# Top.net
KiCad netlist of a schematic drawn in Altium Designer
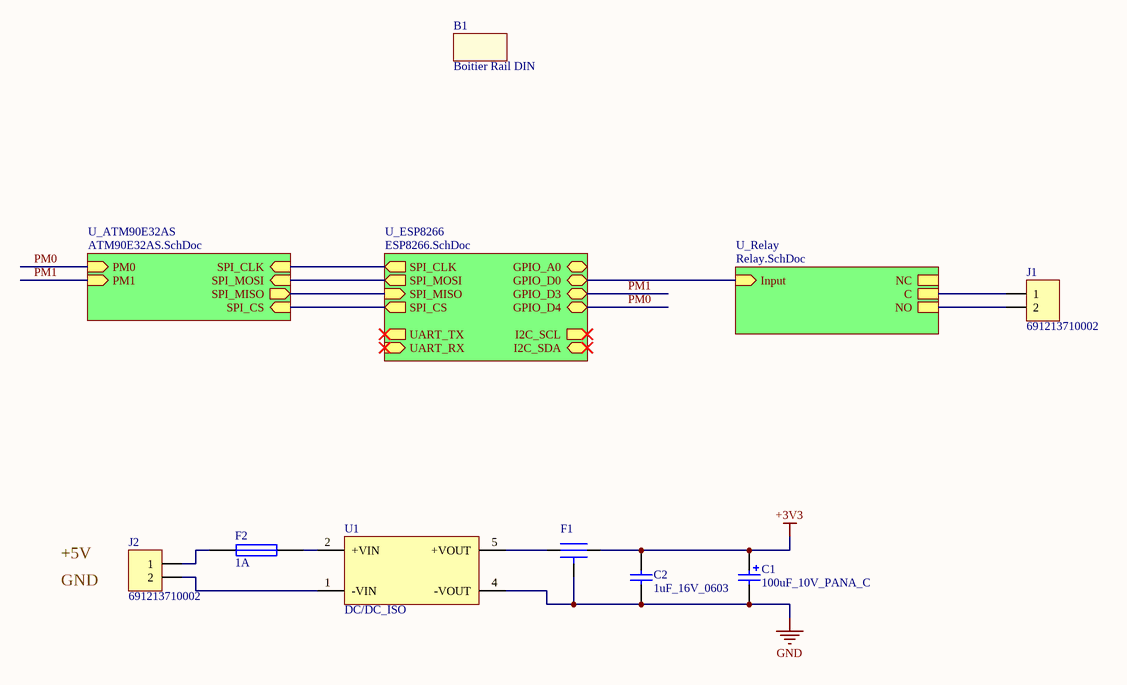
[diagram p0: Top.SchDoc]

(export (version "E")
  (design (tool "Eeschema 10.0.6"))
  (components
    (comp (ref "B1")
      (value "Boitier Rail DIN")
      (description "Part of schematic")
      (fields (field (name "MF") "BUD INDUSTRIES") (field (name "MPN") "DMB4771"))
      (libsource (lib "Common") (part "Component"))
    )
    (comp (ref "C1")
      (value "100uF_10V_PANA_C")
      (footprint "CAP_PANA_C")
      (description "Polarized Capacitor (Radial)")
      (fields (field (name "MF") "PANASONIC ELECTRONIC COMPONENTS") (field (name "MPN") "EEE1AA101WR"))
      (libsource (lib "Common") (part "Cap Pol"))
    )
    (comp (ref "C2")
      (value "1uF_16V_0603")
      (footprint "C0603")
      (description "Capacitor")
      (fields (field (name "MF") "WURTH ELEKTRONIK") (field (name "MPN") "885012106017"))
      (libsource (lib "Common") (part "Cap"))
    )
    (comp (ref "F1")
      (value "EMI")
      (footprint "EMIFIL_0603")
      (description "FILTER CAP 0.1UF 2A 16V 0603")
      (fields (field (name "MF") "MURATA") (field (name "MPN") "NFM18PC104R1C3D"))
      (libsource (lib "Common") (part "EMIFIL_0603"))
    )
    (comp (ref "F2")
      (value "1A")
      (footprint "R0603")
      (description "Fuse")
      (fields (field (name "MF") "MULTICOMP") (field (name "MPN") "MCCFB0603TFF/1"))
      (libsource (lib "Miscellaneous Devices") (part "Fuse 1"))
    )
    (comp (ref "J1")
      (value "691213710002")
      (footprint "691213710002")
      (description "WR-TBL Horizontal Entry Modular with Rising Cage Clamp,Serie 213 - 5.00 mm")
      (fields (field (name "MF") "Wurth Elektronik"))
      (libsource (lib "") (part "691213710002_1"))
    )
    (comp (ref "J2")
      (value "691213710002")
      (footprint "691213710002")
      (description "WR-TBL Horizontal Entry Modular with Rising Cage Clamp,Serie 213 - 5.00 mm")
      (fields (field (name "MF") "Wurth Elektronik"))
      (libsource (lib "WE_WR-TBL_Rising Cage System_5.00 mm_rev15d") (part "691213710002"))
    )
    (comp (ref "U1")
      (value "DC/DC_ISO")
      (footprint "R1SE")
      (description "CONVERTER DC/DC ISOLATED")
      (fields (field (name "MF") "XP POWER") (field (name "MPN") "ISH0503A"))
      (libsource (lib "Common") (part "DC/DC_ISO"))
    )
  )
  (nets
    (net (code "1") (name "+3V3") (class "Default")
      (node (ref "C1") (pin "1") (pinfunction "1_1") (pintype "passive"))
      (node (ref "C2") (pin "2") (pinfunction "2_2") (pintype "passive"))
      (node (ref "F1") (pin "1") (pinfunction "1_1") (pintype "passive"))
    )
    (net (code "2") (name "/C") (class "Default")
      (node (ref "J1") (pin "1") (pinfunction "1_1") (pintype "passive"))
    )
    (net (code "8") (name "/NO") (class "Default")
      (node (ref "J1") (pin "2") (pinfunction "2_2") (pintype "passive"))
    )
    (net (code "17") (name "GND") (class "Default")
      (node (ref "C1") (pin "2") (pinfunction "2_2") (pintype "passive"))
      (node (ref "C2") (pin "1") (pinfunction "1_1") (pintype "passive"))
      (node (ref "F1") (pin "GND") (pinfunction "GND_GND") (pintype "passive"))
      (node (ref "U1") (pin "4") (pinfunction "-VOUT_4") (pintype "power_in"))
    )
    (net (code "18") (name "Net-(F2-Pad2)") (class "Default")
      (node (ref "F2") (pin "2") (pinfunction "2_2") (pintype "passive"))
      (node (ref "J2") (pin "1") (pinfunction "1_1") (pintype "passive"))
    )
    (net (code "19") (name "Net-(U1-+VIN)") (class "Default")
      (node (ref "F2") (pin "1") (pinfunction "1_1") (pintype "passive"))
      (node (ref "U1") (pin "2") (pinfunction "+VIN_2") (pintype "power_in"))
    )
    (net (code "20") (name "Net-(U1-+VOUT)") (class "Default")
      (node (ref "F1") (pin "2") (pinfunction "2_2") (pintype "passive"))
      (node (ref "U1") (pin "5") (pinfunction "+VOUT_5") (pintype "power_in"))
    )
    (net (code "21") (name "Net-(U1--VIN)") (class "Default")
      (node (ref "J2") (pin "2") (pinfunction "2_2") (pintype "passive"))
      (node (ref "U1") (pin "1") (pinfunction "-VIN_1") (pintype "power_in"))
    )
    (net (code "22") (name "unconnected-(U1-NC-Pad3)") (class "Default")
      (node (ref "U1") (pin "3") (pinfunction "NC_3") (pintype "tri_state"))
    )
    (net (code "23") (name "unconnected-(U1-NC-Pad6)") (class "Default")
      (node (ref "U1") (pin "6") (pinfunction "NC_6") (pintype "tri_state"))
    )
    (net (code "24") (name "unconnected-(U1-NC-Pad7)") (class "Default")
      (node (ref "U1") (pin "7") (pinfunction "NC_7") (pintype "tri_state"))
    )
    (net (code "25") (name "unconnected-(U1-NC-Pad8)") (class "Default")
      (node (ref "U1") (pin "8") (pinfunction "NC_8") (pintype "tri_state"))
    )
  )
)
